# MCU.net
KiCad netlist of a schematic drawn in Altium Designer
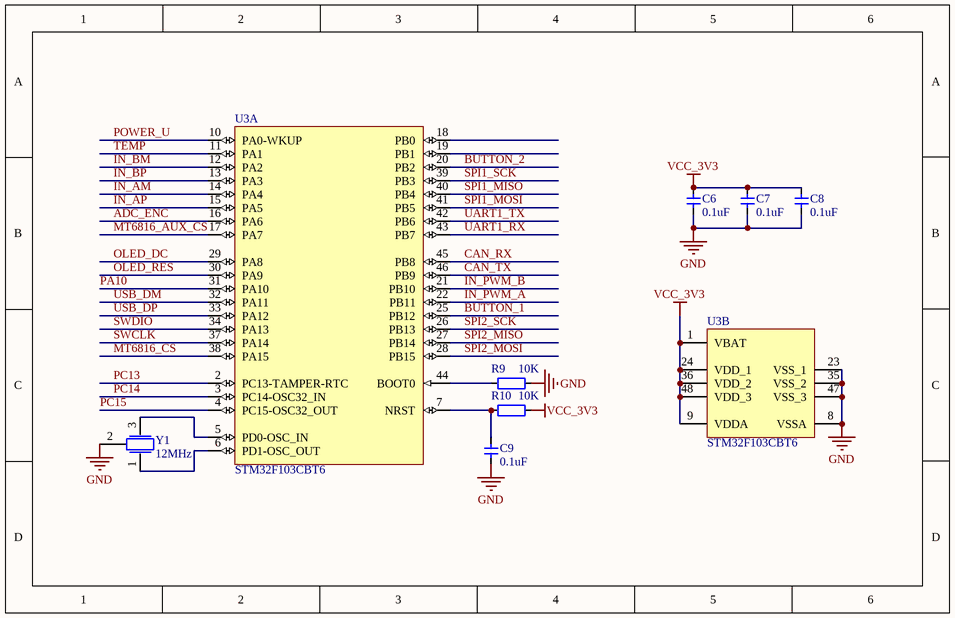
[diagram p0: MCU.SchDoc]

(export (version "E")
  (design (tool "Eeschema 10.0.6"))
  (components
    (comp (ref "C6")
      (value "0.1uF")
      (footprint "CAP_0402")
      (description "Capacitor")
      (libsource (lib "MyPcbLib") (part "电容-0402"))
    )
    (comp (ref "C7")
      (value "0.1uF")
      (footprint "CAP_0402")
      (description "Capacitor")
      (libsource (lib "MyPcbLib") (part "电容-0402"))
    )
    (comp (ref "C8")
      (value "0.1uF")
      (footprint "CAP_0402")
      (description "Capacitor")
      (libsource (lib "MyPcbLib") (part "电容-0402"))
    )
    (comp (ref "C9")
      (value "0.1uF")
      (footprint "CAP_0402")
      (description "Capacitor")
      (libsource (lib "MyPcbLib") (part "电容-0402"))
    )
    (comp (ref "R9")
      (value "10K")
      (footprint "RES_0402")
      (description "Resistor")
      (libsource (lib "MyPcbLib") (part "电阻-0402"))
    )
    (comp (ref "R10")
      (value "10K")
      (footprint "RES_0402")
      (description "Resistor")
      (libsource (lib "MyPcbLib") (part "电阻-0402"))
    )
    (comp (ref "U3")
      (value "STM32F103CBT6")
      (footprint "LQFP-48")
      (libsource (lib "STMicroelectronics STM32 F1") (part "STM32F103CBT6"))
    )
    (comp (ref "Y1")
      (value "12MHz")
      (footprint "晶振-3P")
      (description "村田贴片")
      (libsource (lib "MyPcbLib") (part "晶振-3Pin"))
    )
  )
  (nets
    (net (code "1") (name "/ADC_ENC") (class "Default")
      (node (ref "U3") (pin "16") (pinfunction "PA6_16") (pintype "bidirectional"))
    )
    (net (code "2") (name "/BUTTON_1") (class "Default")
      (node (ref "U3") (pin "25") (pinfunction "PB12_25") (pintype "bidirectional"))
    )
    (net (code "3") (name "/BUTTON_2") (class "Default")
      (node (ref "U3") (pin "20") (pinfunction "PB2_20") (pintype "bidirectional"))
    )
    (net (code "4") (name "/CAN_RX") (class "Default")
      (node (ref "U3") (pin "45") (pinfunction "PB8_45") (pintype "bidirectional"))
    )
    (net (code "5") (name "/CAN_TX") (class "Default")
      (node (ref "U3") (pin "46") (pinfunction "PB9_46") (pintype "bidirectional"))
    )
    (net (code "6") (name "/IN_AM") (class "Default")
      (node (ref "U3") (pin "14") (pinfunction "PA4_14") (pintype "bidirectional"))
    )
    (net (code "7") (name "/IN_AP") (class "Default")
      (node (ref "U3") (pin "15") (pinfunction "PA5_15") (pintype "bidirectional"))
    )
    (net (code "8") (name "/IN_BM") (class "Default")
      (node (ref "U3") (pin "12") (pinfunction "PA2_12") (pintype "bidirectional"))
    )
    (net (code "9") (name "/IN_BP") (class "Default")
      (node (ref "U3") (pin "13") (pinfunction "PA3_13") (pintype "bidirectional"))
    )
    (net (code "10") (name "/IN_PWM_A") (class "Default")
      (node (ref "U3") (pin "22") (pinfunction "PB11_22") (pintype "bidirectional"))
    )
    (net (code "11") (name "/IN_PWM_B") (class "Default")
      (node (ref "U3") (pin "21") (pinfunction "PB10_21") (pintype "bidirectional"))
    )
    (net (code "12") (name "/MT6816_AUX_CS") (class "Default")
      (node (ref "U3") (pin "17") (pinfunction "PA7_17") (pintype "bidirectional"))
    )
    (net (code "13") (name "/MT6816_CS") (class "Default")
      (node (ref "U3") (pin "38") (pinfunction "PA15_38") (pintype "bidirectional"))
    )
    (net (code "14") (name "/OLED_DC") (class "Default")
      (node (ref "U3") (pin "29") (pinfunction "PA8_29") (pintype "bidirectional"))
    )
    (net (code "15") (name "/OLED_RES") (class "Default")
      (node (ref "U3") (pin "30") (pinfunction "PA9_30") (pintype "bidirectional"))
    )
    (net (code "16") (name "/PA10") (class "Default")
      (node (ref "U3") (pin "31") (pinfunction "PA10_31") (pintype "bidirectional"))
    )
    (net (code "17") (name "/PC13") (class "Default")
      (node (ref "U3") (pin "2") (pinfunction "PC13-TAMPER-RTC_2") (pintype "bidirectional"))
    )
    (net (code "18") (name "/PC14") (class "Default")
      (node (ref "U3") (pin "3") (pinfunction "PC14-OSC32_IN_3") (pintype "bidirectional"))
    )
    (net (code "19") (name "/PC15") (class "Default")
      (node (ref "U3") (pin "4") (pinfunction "PC15-OSC32_OUT_4") (pintype "bidirectional"))
    )
    (net (code "20") (name "/POWER_U") (class "Default")
      (node (ref "U3") (pin "10") (pinfunction "PA0-WKUP_10") (pintype "bidirectional"))
    )
    (net (code "21") (name "/SPI1_MISO") (class "Default")
      (node (ref "U3") (pin "40") (pinfunction "PB4_40") (pintype "bidirectional"))
    )
    (net (code "22") (name "/SPI1_MOSI") (class "Default")
      (node (ref "U3") (pin "41") (pinfunction "PB5_41") (pintype "bidirectional"))
    )
    (net (code "23") (name "/SPI1_SCK") (class "Default")
      (node (ref "U3") (pin "39") (pinfunction "PB3_39") (pintype "bidirectional"))
    )
    (net (code "24") (name "/SPI2_MISO") (class "Default")
      (node (ref "U3") (pin "27") (pinfunction "PB14_27") (pintype "bidirectional"))
    )
    (net (code "25") (name "/SPI2_MOSI") (class "Default")
      (node (ref "U3") (pin "28") (pinfunction "PB15_28") (pintype "bidirectional"))
    )
    (net (code "26") (name "/SPI2_SCK") (class "Default")
      (node (ref "U3") (pin "26") (pinfunction "PB13_26") (pintype "bidirectional"))
    )
    (net (code "27") (name "/SWCLK") (class "Default")
      (node (ref "U3") (pin "37") (pinfunction "PA14_37") (pintype "bidirectional"))
    )
    (net (code "28") (name "/SWDIO") (class "Default")
      (node (ref "U3") (pin "34") (pinfunction "PA13_34") (pintype "bidirectional"))
    )
    (net (code "29") (name "/TEMP") (class "Default")
      (node (ref "U3") (pin "11") (pinfunction "PA1_11") (pintype "bidirectional"))
    )
    (net (code "30") (name "/UART1_RX") (class "Default")
      (node (ref "U3") (pin "43") (pinfunction "PB7_43") (pintype "bidirectional"))
    )
    (net (code "31") (name "/UART1_TX") (class "Default")
      (node (ref "U3") (pin "42") (pinfunction "PB6_42") (pintype "bidirectional"))
    )
    (net (code "32") (name "/USB_DM") (class "Default")
      (node (ref "U3") (pin "32") (pinfunction "PA11_32") (pintype "bidirectional"))
    )
    (net (code "33") (name "/USB_DP") (class "Default")
      (node (ref "U3") (pin "33") (pinfunction "PA12_33") (pintype "bidirectional"))
    )
    (net (code "34") (name "GND") (class "Default")
      (node (ref "C6") (pin "1") (pinfunction "1_1") (pintype "passive"))
      (node (ref "C7") (pin "1") (pinfunction "1_1") (pintype "passive"))
      (node (ref "C8") (pin "1") (pinfunction "1_1") (pintype "passive"))
      (node (ref "C9") (pin "1") (pinfunction "1_1") (pintype "passive"))
      (node (ref "R9") (pin "2") (pinfunction "2_2") (pintype "passive"))
      (node (ref "U3") (pin "23") (pinfunction "VSS_1_23") (pintype "power_in"))
      (node (ref "U3") (pin "35") (pinfunction "VSS_2_35") (pintype "power_in"))
      (node (ref "U3") (pin "47") (pinfunction "VSS_3_47") (pintype "power_in"))
      (node (ref "U3") (pin "8") (pinfunction "VSSA_8") (pintype "power_in"))
      (node (ref "Y1") (pin "2") (pinfunction "2_2") (pintype "passive"))
    )
    (net (code "35") (name "Net-(U3A-BOOT0)") (class "Default")
      (node (ref "R9") (pin "1") (pinfunction "1_1") (pintype "passive"))
      (node (ref "U3") (pin "44") (pinfunction "BOOT0_44") (pintype "input"))
    )
    (net (code "36") (name "Net-(U3A-NRST)") (class "Default")
      (node (ref "C9") (pin "2") (pinfunction "2_2") (pintype "passive"))
      (node (ref "R10") (pin "1") (pinfunction "1_1") (pintype "passive"))
      (node (ref "U3") (pin "7") (pinfunction "NRST_7") (pintype "bidirectional"))
    )
    (net (code "37") (name "Net-(U3A-PD0-OSC_IN)") (class "Default")
      (node (ref "U3") (pin "5") (pinfunction "PD0-OSC_IN_5") (pintype "bidirectional"))
      (node (ref "Y1") (pin "3") (pinfunction "3_3") (pintype "passive"))
    )
    (net (code "38") (name "Net-(U3A-PD1-OSC_OUT)") (class "Default")
      (node (ref "U3") (pin "6") (pinfunction "PD1-OSC_OUT_6") (pintype "bidirectional"))
      (node (ref "Y1") (pin "1") (pinfunction "1_1") (pintype "passive"))
    )
    (net (code "39") (name "VCC_3V3") (class "Default")
      (node (ref "C6") (pin "2") (pinfunction "2_2") (pintype "passive"))
      (node (ref "C7") (pin "2") (pinfunction "2_2") (pintype "passive"))
      (node (ref "C8") (pin "2") (pinfunction "2_2") (pintype "passive"))
      (node (ref "R10") (pin "2") (pinfunction "2_2") (pintype "passive"))
      (node (ref "U3") (pin "1") (pinfunction "VBAT_1") (pintype "power_in"))
      (node (ref "U3") (pin "24") (pinfunction "VDD_1_24") (pintype "power_in"))
      (node (ref "U3") (pin "36") (pinfunction "VDD_2_36") (pintype "power_in"))
      (node (ref "U3") (pin "48") (pinfunction "VDD_3_48") (pintype "power_in"))
      (node (ref "U3") (pin "9") (pinfunction "VDDA_9") (pintype "power_in"))
    )
    (net (code "40") (name "unconnected-(U3A-PB0-Pad18)") (class "Default")
      (node (ref "U3") (pin "18") (pinfunction "PB0_18") (pintype "bidirectional"))
    )
    (net (code "41") (name "unconnected-(U3A-PB1-Pad19)") (class "Default")
      (node (ref "U3") (pin "19") (pinfunction "PB1_19") (pintype "bidirectional"))
    )
  )
)
